# Memory.net
KiCad netlist of a schematic drawn in Altium Designer
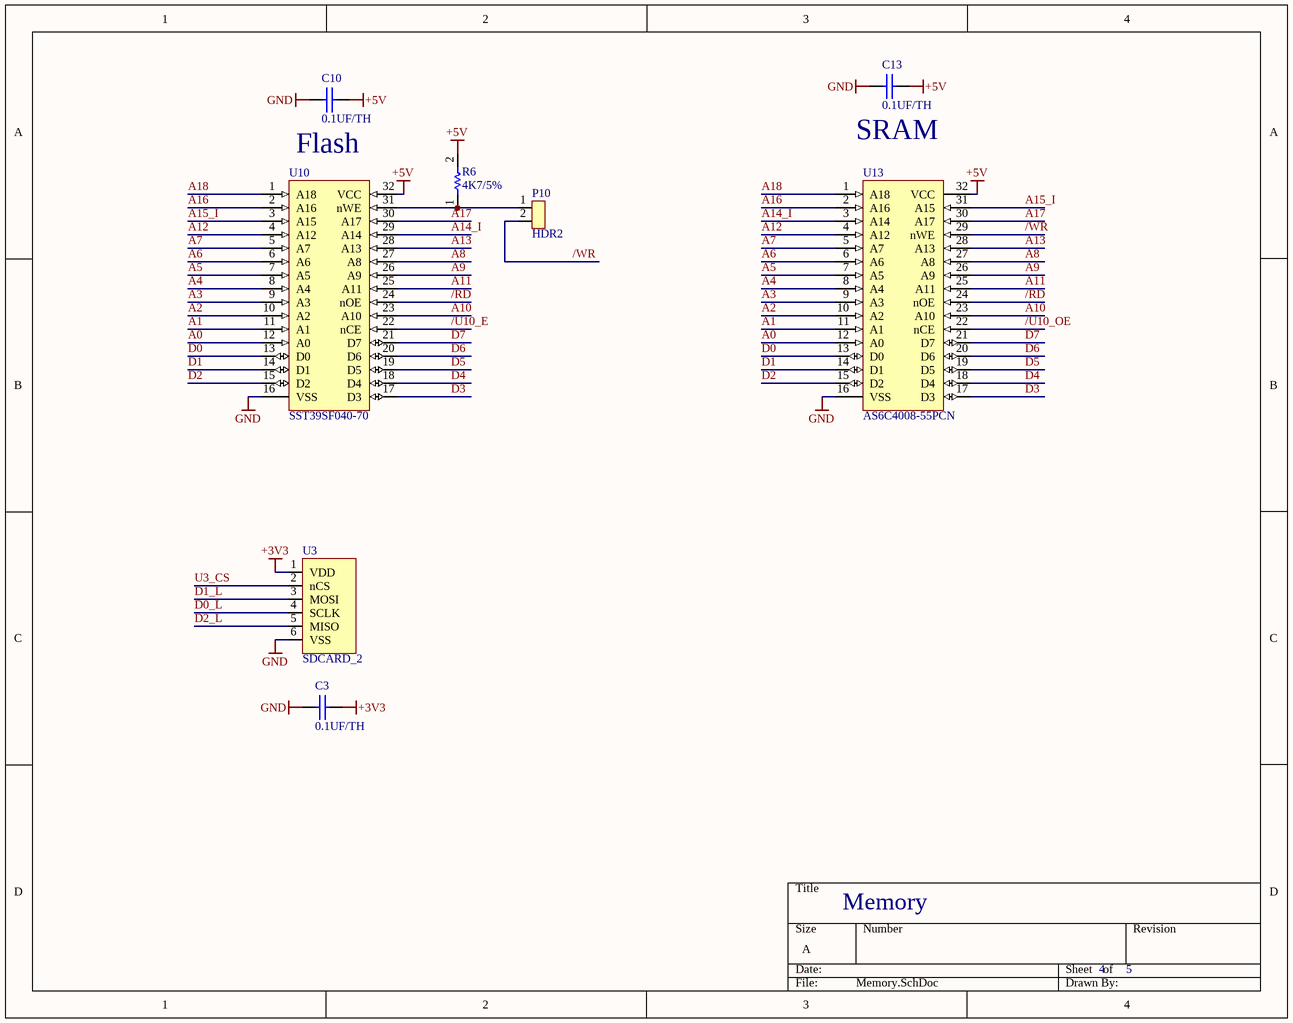
[diagram p0: Memory.SchDoc]

(export (version "E")
  (design (tool "Eeschema 10.0.6"))
  (components
    (comp (ref "C3")
      (value "0.1UF/TH")
      (footprint "CAPH5")
      (description "0.1 µF ±10% 50V Ceramic Capacitor X7R Radial")
      (fields (field (name "MFG") "Vishay"))
      (libsource (lib "CapacitorsTH") (part "0.1UF/TH"))
    )
    (comp (ref "C10")
      (value "0.1UF/TH")
      (footprint "CAPH5")
      (description "0.1 µF ±10% 50V Ceramic Capacitor X7R Radial")
      (fields (field (name "MFG") "Vishay"))
      (libsource (lib "CapacitorsTH") (part "0.1UF/TH"))
    )
    (comp (ref "C13")
      (value "0.1UF/TH")
      (footprint "CAPH5")
      (description "0.1 µF ±10% 50V Ceramic Capacitor X7R Radial")
      (fields (field (name "MFG") "Vishay"))
      (libsource (lib "CapacitorsTH") (part "0.1UF/TH"))
    )
    (comp (ref "P10") (value "HDR2") (footprint "HDR2") (libsource (lib "Connectors") (part "HDR2")))
    (comp (ref "R6")
      (value "4K7/5%")
      (footprint "CF18")
      (description "RES 4.7K OHM 5% 1/8W AXIAL")
      (fields (field (name "MFG") "Stackpole"))
      (libsource (lib "ResistorsTH") (part "4K7/5%"))
    )
    (comp (ref "U3")
      (value "SDCARD_2")
      (footprint "SDMODULE1_FLIPPED")
      (description "Micro SD card module")
      (fields (field (name "MFG") "TE"))
      (libsource (lib "Connectors") (part "SDCARD_2"))
    )
    (comp (ref "U10")
      (value "SST39SF040-70")
      (footprint "DIP32")
      (description "FLASH Memory IC 4Mbit Parallel 70 ns 32-PDIP")
      (fields (field (name "MFG") "Microchip"))
      (libsource (lib "DigitalIC") (part "SST39SF040-70"))
    )
    (comp (ref "U13")
      (value "AS6C4008-55PCN")
      (footprint "DIP32")
      (description "SRAM - Asynchronous Memory IC 4Mb (512K x 8) Parallel 55 ns 32-DIP")
      (fields (field (name "MFG") "Alliance Memory, Inc."))
      (libsource (lib "DigitalIC") (part "AS6C4008-55PCN"))
    )
  )
  (nets
    (net (code "1") (name "+3V3") (class "Default")
      (node (ref "C3") (pin "2") (pintype "passive"))
      (node (ref "U3") (pin "1") (pinfunction "VDD_1") (pintype "passive"))
    )
    (net (code "2") (name "+5V") (class "Default")
      (node (ref "C10") (pin "2") (pintype "passive"))
      (node (ref "C13") (pin "2") (pintype "passive"))
      (node (ref "R6") (pin "2") (pinfunction "2_2") (pintype "passive"))
      (node (ref "U10") (pin "32") (pinfunction "VCC_32") (pintype "input"))
      (node (ref "U13") (pin "32") (pinfunction "VCC_32") (pintype "power_in"))
    )
    (net (code "3") (name "/A0") (class "Default")
      (node (ref "U10") (pin "12") (pinfunction "A0_12") (pintype "input"))
      (node (ref "U13") (pin "12") (pinfunction "A0_12") (pintype "input"))
    )
    (net (code "4") (name "/A1") (class "Default")
      (node (ref "U10") (pin "11") (pinfunction "A1_11") (pintype "input"))
      (node (ref "U13") (pin "11") (pinfunction "A1_11") (pintype "input"))
    )
    (net (code "5") (name "/A2") (class "Default")
      (node (ref "U10") (pin "10") (pinfunction "A2_10") (pintype "input"))
      (node (ref "U13") (pin "10") (pinfunction "A2_10") (pintype "input"))
    )
    (net (code "6") (name "/A3") (class "Default")
      (node (ref "U10") (pin "9") (pinfunction "A3_9") (pintype "input"))
      (node (ref "U13") (pin "9") (pinfunction "A3_9") (pintype "input"))
    )
    (net (code "7") (name "/A4") (class "Default")
      (node (ref "U10") (pin "8") (pinfunction "A4_8") (pintype "input"))
      (node (ref "U13") (pin "8") (pinfunction "A4_8") (pintype "input"))
    )
    (net (code "8") (name "/A5") (class "Default")
      (node (ref "U10") (pin "7") (pinfunction "A5_7") (pintype "input"))
      (node (ref "U13") (pin "7") (pinfunction "A5_7") (pintype "input"))
    )
    (net (code "9") (name "/A6") (class "Default")
      (node (ref "U10") (pin "6") (pinfunction "A6_6") (pintype "input"))
      (node (ref "U13") (pin "6") (pinfunction "A6_6") (pintype "input"))
    )
    (net (code "10") (name "/A7") (class "Default")
      (node (ref "U10") (pin "5") (pinfunction "A7_5") (pintype "input"))
      (node (ref "U13") (pin "5") (pinfunction "A7_5") (pintype "input"))
    )
    (net (code "11") (name "/A8") (class "Default")
      (node (ref "U10") (pin "27") (pinfunction "A8_27") (pintype "input"))
      (node (ref "U13") (pin "27") (pinfunction "A8_27") (pintype "input"))
    )
    (net (code "12") (name "/A9") (class "Default")
      (node (ref "U10") (pin "26") (pinfunction "A9_26") (pintype "input"))
      (node (ref "U13") (pin "26") (pinfunction "A9_26") (pintype "input"))
    )
    (net (code "13") (name "/A10") (class "Default")
      (node (ref "U10") (pin "23") (pinfunction "A10_23") (pintype "input"))
      (node (ref "U13") (pin "23") (pinfunction "A10_23") (pintype "input"))
    )
    (net (code "14") (name "/A11") (class "Default")
      (node (ref "U10") (pin "25") (pinfunction "A11_25") (pintype "input"))
      (node (ref "U13") (pin "25") (pinfunction "A11_25") (pintype "input"))
    )
    (net (code "15") (name "/A12") (class "Default")
      (node (ref "U10") (pin "4") (pinfunction "A12_4") (pintype "input"))
      (node (ref "U13") (pin "4") (pinfunction "A12_4") (pintype "input"))
    )
    (net (code "16") (name "/A13") (class "Default")
      (node (ref "U10") (pin "28") (pinfunction "A13_28") (pintype "input"))
      (node (ref "U13") (pin "28") (pinfunction "A13_28") (pintype "input"))
    )
    (net (code "17") (name "/A14_I") (class "Default")
      (node (ref "U10") (pin "29") (pinfunction "A14_29") (pintype "input"))
      (node (ref "U13") (pin "3") (pinfunction "A14_3") (pintype "input"))
    )
    (net (code "18") (name "/A15_I") (class "Default")
      (node (ref "U10") (pin "3") (pinfunction "A15_3") (pintype "input"))
      (node (ref "U13") (pin "31") (pinfunction "A15_31") (pintype "input"))
    )
    (net (code "19") (name "/A16") (class "Default")
      (node (ref "U10") (pin "2") (pinfunction "A16_2") (pintype "input"))
      (node (ref "U13") (pin "2") (pinfunction "A16_2") (pintype "input"))
    )
    (net (code "20") (name "/A17") (class "Default")
      (node (ref "U10") (pin "30") (pinfunction "A17_30") (pintype "input"))
      (node (ref "U13") (pin "30") (pinfunction "A17_30") (pintype "input"))
    )
    (net (code "21") (name "/A18") (class "Default")
      (node (ref "U10") (pin "1") (pinfunction "A18_1") (pintype "input"))
      (node (ref "U13") (pin "1") (pinfunction "A18_1") (pintype "input"))
    )
    (net (code "22") (name "/D0") (class "Default")
      (node (ref "U10") (pin "13") (pinfunction "D0_13") (pintype "bidirectional"))
      (node (ref "U13") (pin "13") (pinfunction "D0_13") (pintype "bidirectional"))
    )
    (net (code "23") (name "/D0_L") (class "Default")
      (node (ref "U3") (pin "4") (pinfunction "SCLK_4") (pintype "passive"))
    )
    (net (code "24") (name "/D1") (class "Default")
      (node (ref "U10") (pin "14") (pinfunction "D1_14") (pintype "bidirectional"))
      (node (ref "U13") (pin "14") (pinfunction "D1_14") (pintype "bidirectional"))
    )
    (net (code "25") (name "/D1_L") (class "Default")
      (node (ref "U3") (pin "3") (pinfunction "MOSI_3") (pintype "passive"))
    )
    (net (code "26") (name "/D2") (class "Default")
      (node (ref "U10") (pin "15") (pinfunction "D2_15") (pintype "bidirectional"))
      (node (ref "U13") (pin "15") (pinfunction "D2_15") (pintype "bidirectional"))
    )
    (net (code "27") (name "/D2_L") (class "Default")
      (node (ref "U3") (pin "5") (pinfunction "MISO_5") (pintype "passive"))
    )
    (net (code "28") (name "/D3") (class "Default")
      (node (ref "U10") (pin "17") (pinfunction "D3_17") (pintype "bidirectional"))
      (node (ref "U13") (pin "17") (pinfunction "D3_17") (pintype "bidirectional"))
    )
    (net (code "29") (name "/D4") (class "Default")
      (node (ref "U10") (pin "18") (pinfunction "D4_18") (pintype "bidirectional"))
      (node (ref "U13") (pin "18") (pinfunction "D4_18") (pintype "bidirectional"))
    )
    (net (code "30") (name "/D5") (class "Default")
      (node (ref "U10") (pin "19") (pinfunction "D5_19") (pintype "bidirectional"))
      (node (ref "U13") (pin "19") (pinfunction "D5_19") (pintype "bidirectional"))
    )
    (net (code "31") (name "/D6") (class "Default")
      (node (ref "U10") (pin "20") (pinfunction "D6_20") (pintype "bidirectional"))
      (node (ref "U13") (pin "20") (pinfunction "D6_20") (pintype "bidirectional"))
    )
    (net (code "32") (name "/D7") (class "Default")
      (node (ref "U10") (pin "21") (pinfunction "D7_21") (pintype "bidirectional"))
      (node (ref "U13") (pin "21") (pinfunction "D7_21") (pintype "bidirectional"))
    )
    (net (code "33") (name "/U3_CS") (class "Default")
      (node (ref "U3") (pin "2") (pinfunction "nCS_2") (pintype "passive"))
    )
    (net (code "34") (name "/{slash}RD") (class "Default")
      (node (ref "U10") (pin "24") (pinfunction "nOE_24") (pintype "input"))
      (node (ref "U13") (pin "24") (pinfunction "nOE_24") (pintype "input"))
    )
    (net (code "35") (name "/{slash}U10_E") (class "Default")
      (node (ref "U10") (pin "22") (pinfunction "nCE_22") (pintype "input"))
    )
    (net (code "36") (name "/{slash}U10_OE") (class "Default")
      (node (ref "U13") (pin "22") (pinfunction "nCE_22") (pintype "input"))
    )
    (net (code "37") (name "/{slash}WR") (class "Default")
      (node (ref "P10") (pin "2") (pintype "passive"))
      (node (ref "U13") (pin "29") (pinfunction "nWE_29") (pintype "input"))
    )
    (net (code "38") (name "GND") (class "Default")
      (node (ref "C10") (pin "1") (pintype "passive"))
      (node (ref "C13") (pin "1") (pintype "passive"))
      (node (ref "C3") (pin "1") (pintype "passive"))
      (node (ref "U10") (pin "16") (pinfunction "VSS_16") (pintype "power_in"))
      (node (ref "U13") (pin "16") (pinfunction "VSS_16") (pintype "power_in"))
      (node (ref "U3") (pin "6") (pinfunction "VSS_6") (pintype "passive"))
    )
    (net (code "39") (name "Net-(U10-nWE)") (class "Default")
      (node (ref "P10") (pin "1") (pintype "passive"))
      (node (ref "R6") (pin "1") (pinfunction "1_1") (pintype "passive"))
      (node (ref "U10") (pin "31") (pinfunction "nWE_31") (pintype "input"))
    )
  )
)
